# tracer-jigu.net
KiCad netlist of a schematic drawn in EAGLE
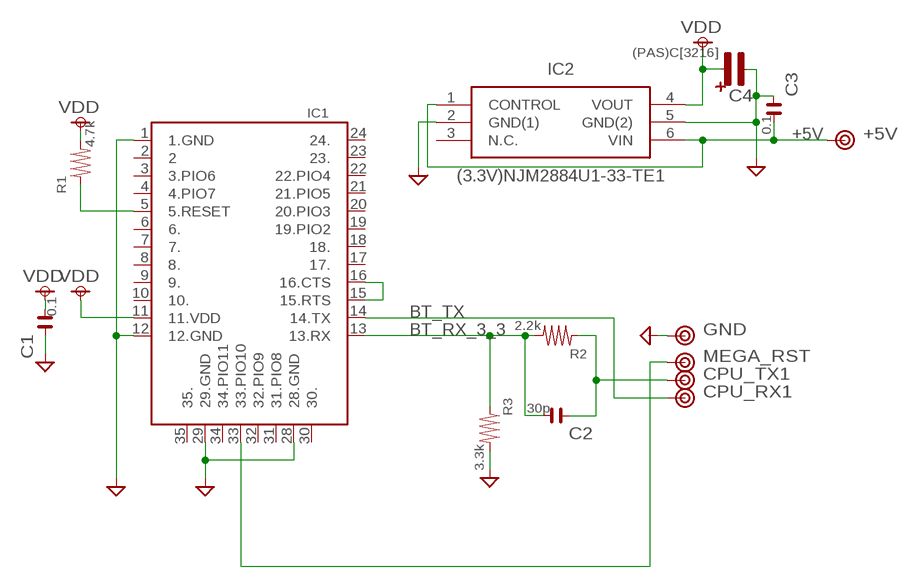
[diagram p0: schematic, sheet 1]

(export (version "E")
  (design (tool "Eeschema 10.0.6"))
  (components
    (comp (ref "+5V")
      (value "TP-HOLE")
      (footprint "eagle-import:TP-HOLE")
      (libsource (lib "eagle-import") (part "TP-HOLE"))
    )
    (comp (ref "C1")
      (value "0.1")
      (footprint "eagle-import:1608NEW")
      (libsource (lib "eagle-import") (part "(PAS)C[1608]"))
    )
    (comp (ref "C2")
      (value "30p")
      (footprint "eagle-import:1608NEW")
      (libsource (lib "eagle-import") (part "(PAS)C[1608]"))
    )
    (comp (ref "C3")
      (value "0.1")
      (footprint "eagle-import:1608NEW")
      (libsource (lib "eagle-import") (part "(PAS)C[1608]"))
    )
    (comp (ref "C4")
      (value "(PAS)C[3216]")
      (footprint "eagle-import:3216")
      (libsource (lib "eagle-import") (part "(PAS)C[3216]"))
    )
    (comp (ref "CPU_RX1")
      (value "TP-HOLE")
      (footprint "eagle-import:TP-HOLE")
      (libsource (lib "eagle-import") (part "TP-HOLE"))
    )
    (comp (ref "CPU_TX1")
      (value "TP-HOLE")
      (footprint "eagle-import:TP-HOLE")
      (libsource (lib "eagle-import") (part "TP-HOLE"))
    )
    (comp (ref "GND")
      (value "TP-HOLE")
      (footprint "eagle-import:TP-HOLE")
      (libsource (lib "eagle-import") (part "TP-HOLE"))
    )
    (comp (ref "IC1")
      (value "RN-42-BT")
      (footprint "eagle-import:RN42-BT-PAC")
      (libsource (lib "eagle-import") (part "RN-42-BT"))
    )
    (comp (ref "IC2")
      (value "(3.3V)NJM2884U1-33-TE1")
      (footprint "eagle-import:SOT-89-5-1")
      (fields
        (field (name "MANUFACTURER_PART_NUMBER") "NJM2884U1-33-TE1")
        (field (name "RS_PART_NUMBER") "7139366P")
      )
      (libsource (lib "eagle-import") (part "(3.3V)NJM2884U1-33-TE1"))
    )
    (comp (ref "MEGA_RST")
      (value "TP-HOLE")
      (footprint "eagle-import:TP-HOLE")
      (libsource (lib "eagle-import") (part "TP-HOLE"))
    )
    (comp (ref "R1")
      (value "4.7k")
      (footprint "eagle-import:1608NEW")
      (libsource (lib "eagle-import") (part "(PAS)R[1608]"))
    )
    (comp (ref "R2")
      (value "2.2k")
      (footprint "eagle-import:1608NEW")
      (libsource (lib "eagle-import") (part "(PAS)R[1608]"))
    )
    (comp (ref "R3")
      (value "3.3k")
      (footprint "eagle-import:1608NEW")
      (libsource (lib "eagle-import") (part "(PAS)R[1608]"))
    )
  )
  (nets
    (net (code "1") (name "/+5V") (class "Default")
      (node (ref "+5V") (pin "1") (pinfunction "P$1_1") (pintype "passive"))
      (node (ref "C3") (pin "2") (pinfunction "P$2_2") (pintype "passive"))
      (node (ref "IC2") (pin "1") (pinfunction "CONTROL_1") (pintype "passive"))
      (node (ref "IC2") (pin "6") (pinfunction "VIN_6") (pintype "passive"))
    )
    (net (code "2") (name "/BT_RX_3_3") (class "Default")
      (node (ref "C2") (pin "2") (pinfunction "P$2_2") (pintype "passive"))
      (node (ref "IC1") (pin "13") (pinfunction "13.RX_13") (pintype "passive"))
      (node (ref "R2") (pin "2") (pinfunction "2_2") (pintype "passive"))
      (node (ref "R3") (pin "1") (pinfunction "1_1") (pintype "passive"))
    )
    (net (code "3") (name "/BT_TX") (class "Default")
      (node (ref "CPU_RX1") (pin "1") (pinfunction "P$1_1") (pintype "passive"))
      (node (ref "IC1") (pin "14") (pinfunction "14.TX_14") (pintype "passive"))
    )
    (net (code "4") (name "GND") (class "Default")
      (node (ref "C1") (pin "1") (pinfunction "P$1_1") (pintype "passive"))
      (node (ref "C3") (pin "1") (pinfunction "P$1_1") (pintype "passive"))
      (node (ref "C4") (pin "2") (pinfunction "M_2") (pintype "passive"))
      (node (ref "GND") (pin "1") (pinfunction "P$1_1") (pintype "passive"))
      (node (ref "IC1") (pin "1") (pinfunction "1.GND_1") (pintype "passive"))
      (node (ref "IC1") (pin "12") (pinfunction "12.GND_12") (pintype "passive"))
      (node (ref "IC1") (pin "28") (pinfunction "28.GND_28") (pintype "passive"))
      (node (ref "IC1") (pin "29") (pinfunction "29.GND_29") (pintype "passive"))
      (node (ref "IC2") (pin "2") (pinfunction "GND(1)_2") (pintype "passive"))
      (node (ref "IC2") (pin "5") (pinfunction "GND(2)_5") (pintype "passive"))
      (node (ref "R3") (pin "2") (pinfunction "2_2") (pintype "passive"))
    )
    (net (code "5") (name "Net-(C2-P$1)") (class "Default")
      (node (ref "C2") (pin "1") (pinfunction "P$1_1") (pintype "passive"))
      (node (ref "CPU_TX1") (pin "1") (pinfunction "P$1_1") (pintype "passive"))
      (node (ref "R2") (pin "1") (pinfunction "1_1") (pintype "passive"))
    )
    (net (code "6") (name "Net-(IC1-5.RESET)") (class "Default")
      (node (ref "IC1") (pin "5") (pinfunction "5.RESET_5") (pintype "passive"))
      (node (ref "R1") (pin "1") (pinfunction "1_1") (pintype "passive"))
    )
    (net (code "7") (name "Net-(IC1-15.RTS)") (class "Default")
      (node (ref "IC1") (pin "15") (pinfunction "15.RTS_15") (pintype "passive"))
      (node (ref "IC1") (pin "16") (pinfunction "16.CTS_16") (pintype "passive"))
    )
    (net (code "8") (name "Net-(IC1-33.PIO10)") (class "Default")
      (node (ref "IC1") (pin "33") (pinfunction "33.PIO10_33") (pintype "passive"))
      (node (ref "MEGA_RST") (pin "1") (pinfunction "P$1_1") (pintype "passive"))
    )
    (net (code "9") (name "VDD") (class "Default")
      (node (ref "C1") (pin "2") (pinfunction "P$2_2") (pintype "passive"))
      (node (ref "C4") (pin "1") (pinfunction "P_1") (pintype "passive"))
      (node (ref "IC1") (pin "11") (pinfunction "11.VDD_11") (pintype "passive"))
      (node (ref "IC2") (pin "4") (pinfunction "VOUT_4") (pintype "passive"))
      (node (ref "R1") (pin "2") (pinfunction "2_2") (pintype "passive"))
    )
    (net (code "10") (name "unconnected-(IC1-3.PIO6-Pad3)") (class "Default")
      (node (ref "IC1") (pin "3") (pinfunction "3.PIO6_3") (pintype "passive"))
    )
    (net (code "11") (name "unconnected-(IC1-4.PIO7-Pad4)") (class "Default")
      (node (ref "IC1") (pin "4") (pinfunction "4.PIO7_4") (pintype "passive"))
    )
    (net (code "12") (name "unconnected-(IC1-6.-Pad6)") (class "Default")
      (node (ref "IC1") (pin "6") (pinfunction "6._6") (pintype "passive"))
    )
    (net (code "13") (name "unconnected-(IC1-7.-Pad7)") (class "Default")
      (node (ref "IC1") (pin "7") (pinfunction "7._7") (pintype "passive"))
    )
    (net (code "14") (name "unconnected-(IC1-8.-Pad8)") (class "Default")
      (node (ref "IC1") (pin "8") (pinfunction "8._8") (pintype "passive"))
    )
    (net (code "15") (name "unconnected-(IC1-9.-Pad9)") (class "Default")
      (node (ref "IC1") (pin "9") (pinfunction "9._9") (pintype "passive"))
    )
    (net (code "16") (name "unconnected-(IC1-10.-Pad10)") (class "Default")
      (node (ref "IC1") (pin "10") (pinfunction "10._10") (pintype "passive"))
    )
    (net (code "17") (name "unconnected-(IC1-17.-Pad17)") (class "Default")
      (node (ref "IC1") (pin "17") (pinfunction "17._17") (pintype "passive"))
    )
    (net (code "18") (name "unconnected-(IC1-18.-Pad18)") (class "Default")
      (node (ref "IC1") (pin "18") (pinfunction "18._18") (pintype "passive"))
    )
    (net (code "19") (name "unconnected-(IC1-19.PIO2-Pad19)") (class "Default")
      (node (ref "IC1") (pin "19") (pinfunction "19.PIO2_19") (pintype "passive"))
    )
    (net (code "20") (name "unconnected-(IC1-20.PIO3-Pad20)") (class "Default")
      (node (ref "IC1") (pin "20") (pinfunction "20.PIO3_20") (pintype "passive"))
    )
    (net (code "21") (name "unconnected-(IC1-21.PIO5-Pad21)") (class "Default")
      (node (ref "IC1") (pin "21") (pinfunction "21.PIO5_21") (pintype "passive"))
    )
    (net (code "22") (name "unconnected-(IC1-22.PIO4-Pad22)") (class "Default")
      (node (ref "IC1") (pin "22") (pinfunction "22.PIO4_22") (pintype "passive"))
    )
    (net (code "23") (name "unconnected-(IC1-23.-Pad23)") (class "Default")
      (node (ref "IC1") (pin "23") (pinfunction "23._23") (pintype "passive"))
    )
    (net (code "24") (name "unconnected-(IC1-24.-Pad24)") (class "Default")
      (node (ref "IC1") (pin "24") (pinfunction "24._24") (pintype "passive"))
    )
    (net (code "25") (name "unconnected-(IC1-30.-Pad30)") (class "Default")
      (node (ref "IC1") (pin "30") (pinfunction "30._30") (pintype "passive"))
    )
    (net (code "26") (name "unconnected-(IC1-31.PIO8-Pad31)") (class "Default")
      (node (ref "IC1") (pin "31") (pinfunction "31.PIO8_31") (pintype "passive"))
    )
    (net (code "27") (name "unconnected-(IC1-32.PIO9-Pad32)") (class "Default")
      (node (ref "IC1") (pin "32") (pinfunction "32.PIO9_32") (pintype "passive"))
    )
    (net (code "28") (name "unconnected-(IC1-34.PIO11-Pad34)") (class "Default")
      (node (ref "IC1") (pin "34") (pinfunction "34.PIO11_34") (pintype "passive"))
    )
    (net (code "29") (name "unconnected-(IC1-35.-Pad35)") (class "Default")
      (node (ref "IC1") (pin "35") (pinfunction "35._35") (pintype "passive"))
    )
    (net (code "30") (name "unconnected-(IC1-Pad2)") (class "Default")
      (node (ref "IC1") (pin "2") (pinfunction "2_2") (pintype "passive"))
    )
    (net (code "31") (name "unconnected-(IC2-N.C.-Pad3)") (class "Default")
      (node (ref "IC2") (pin "3") (pinfunction "N.C._3") (pintype "passive"))
    )
  )
)
